# RH043_2.net
KiCad netlist of a schematic drawn in EAGLE
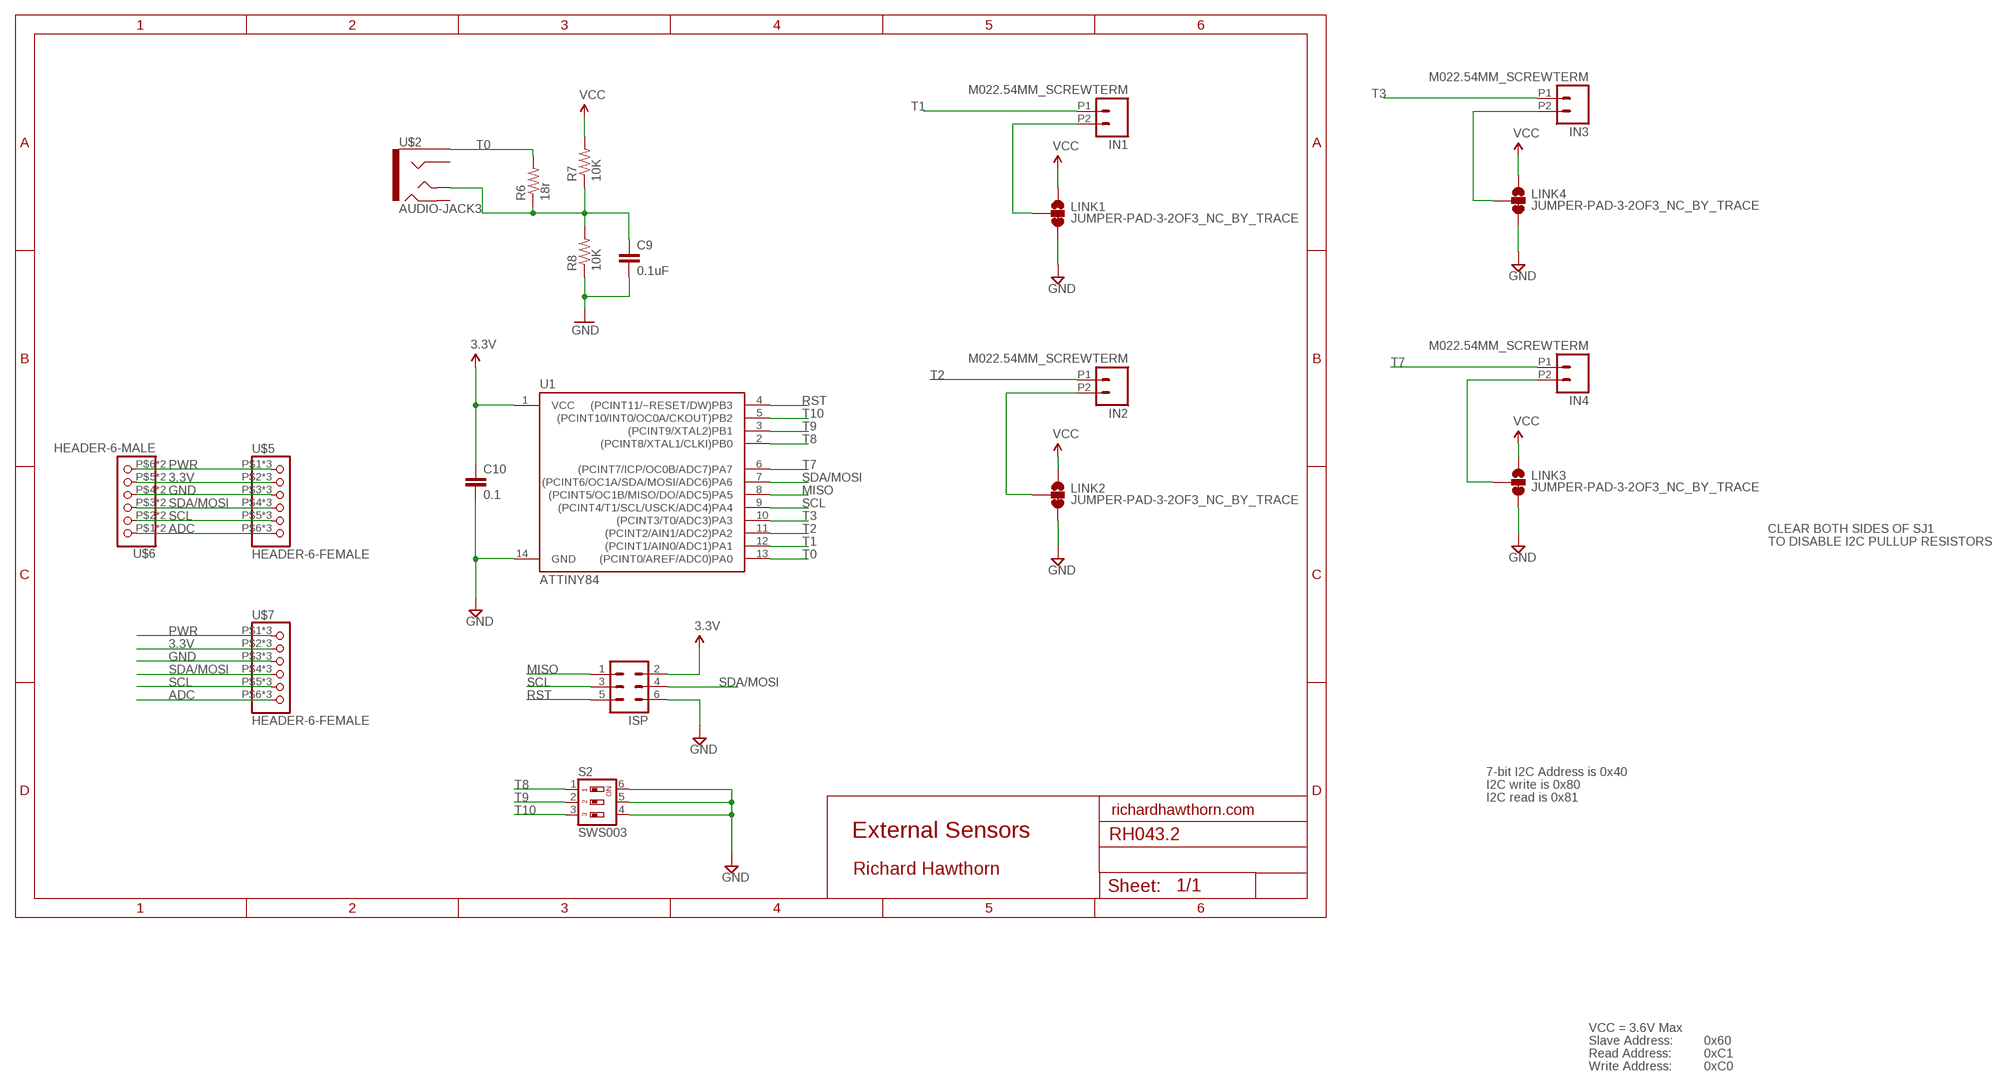
[diagram p0: schematic, sheet 1]

(export (version "E")
  (design (tool "Eeschema 10.0.6"))
  (components
    (comp (ref "C9")
      (value "0.1uF")
      (footprint "eagle-import:0603-CAP")
      (libsource (lib "eagle-import") (part "SparkFun_CAP0603-CAP"))
    )
    (comp (ref "C10")
      (value "0.1")
      (footprint "eagle-import:0603-CAP")
      (libsource (lib "eagle-import") (part "CAP0603-CAP"))
    )
    (comp (ref "IN1")
      (value "M022.54MM_SCREWTERM")
      (footprint "eagle-import:1X02_2.54_SCREWTERM")
      (libsource (lib "eagle-import") (part "M022.54MM_SCREWTERM"))
    )
    (comp (ref "IN2")
      (value "M022.54MM_SCREWTERM")
      (footprint "eagle-import:1X02_2.54_SCREWTERM")
      (libsource (lib "eagle-import") (part "M022.54MM_SCREWTERM"))
    )
    (comp (ref "IN3")
      (value "M022.54MM_SCREWTERM")
      (footprint "eagle-import:1X02_2.54_SCREWTERM")
      (libsource (lib "eagle-import") (part "M022.54MM_SCREWTERM"))
    )
    (comp (ref "IN4")
      (value "M022.54MM_SCREWTERM")
      (footprint "eagle-import:1X02_2.54_SCREWTERM")
      (libsource (lib "eagle-import") (part "M022.54MM_SCREWTERM"))
    )
    (comp (ref "ISP")
      (value "MA03-2")
      (footprint "eagle-import:MA03-2")
      (libsource (lib "eagle-import") (part "MA03-2"))
    )
    (comp (ref "LINK1")
      (value "JUMPER-PAD-3-2OF3_NC_BY_TRACE")
      (footprint "eagle-import:PAD-JUMPER-3-2OF3_NC_BY_TRACE_YES_SILK_FULL_BOX")
      (libsource (lib "eagle-import") (part "JUMPER-PAD-3-2OF3_NC_BY_TRACE"))
    )
    (comp (ref "LINK2")
      (value "JUMPER-PAD-3-2OF3_NC_BY_TRACE")
      (footprint "eagle-import:PAD-JUMPER-3-2OF3_NC_BY_TRACE_YES_SILK_FULL_BOX")
      (libsource (lib "eagle-import") (part "JUMPER-PAD-3-2OF3_NC_BY_TRACE"))
    )
    (comp (ref "LINK3")
      (value "JUMPER-PAD-3-2OF3_NC_BY_TRACE")
      (footprint "eagle-import:PAD-JUMPER-3-2OF3_NC_BY_TRACE_YES_SILK_FULL_BOX")
      (libsource (lib "eagle-import") (part "JUMPER-PAD-3-2OF3_NC_BY_TRACE"))
    )
    (comp (ref "LINK4")
      (value "JUMPER-PAD-3-2OF3_NC_BY_TRACE")
      (footprint "eagle-import:PAD-JUMPER-3-2OF3_NC_BY_TRACE_YES_SILK_FULL_BOX")
      (libsource (lib "eagle-import") (part "JUMPER-PAD-3-2OF3_NC_BY_TRACE"))
    )
    (comp (ref "R6")
      (value "18r")
      (footprint "eagle-import:0603-RES")
      (libsource (lib "eagle-import") (part "RESISTOR0603-RES"))
    )
    (comp (ref "R7")
      (value "10K")
      (footprint "eagle-import:0603-RES")
      (libsource (lib "eagle-import") (part "RESISTOR0603-RES"))
    )
    (comp (ref "R8")
      (value "10K")
      (footprint "eagle-import:0603-RES")
      (libsource (lib "eagle-import") (part "RESISTOR0603-RES"))
    )
    (comp (ref "S2")
      (value "SWS003")
      (footprint "eagle-import:SMS-003")
      (libsource (lib "eagle-import") (part "SWS003"))
    )
    (comp (ref "U$2")
      (value "AUDIO-JACK3")
      (footprint "eagle-import:AUDIO-JACK-TRRS-SMD")
      (libsource (lib "eagle-import") (part "AUDIO-JACK3"))
    )
    (comp (ref "U$5")
      (value "HEADER-6-FEMALE")
      (footprint "eagle-import:2MMHEADER6")
      (libsource (lib "eagle-import") (part "HEADER-6-FEMALE"))
    )
    (comp (ref "U$6")
      (value "HEADER-6-MALE")
      (footprint "eagle-import:2MMHEADERPIN6")
      (libsource (lib "eagle-import") (part "HEADER-6-MALE"))
    )
    (comp (ref "U$7")
      (value "HEADER-6-FEMALE")
      (footprint "eagle-import:2MMHEADER6")
      (libsource (lib "eagle-import") (part "HEADER-6-FEMALE"))
    )
    (comp (ref "U1")
      (value "ATTINY84")
      (footprint "eagle-import:SO14")
      (libsource (lib "eagle-import") (part "ATTINY84"))
    )
  )
  (nets
    (net (code "1") (name "/ADC") (class "Default")
      (node (ref "U$5") (pin "P$14") (pinfunction "6_P$14") (pintype "passive"))
      (node (ref "U$5") (pin "P$22") (pinfunction "6_P$22") (pintype "passive"))
      (node (ref "U$5") (pin "P$6") (pinfunction "6_P$6") (pintype "passive"))
      (node (ref "U$6") (pin "P$1") (pinfunction "1_P$1") (pintype "passive"))
      (node (ref "U$6") (pin "P$9") (pinfunction "1_P$9") (pintype "passive"))
      (node (ref "U$7") (pin "P$14") (pinfunction "6_P$14") (pintype "passive"))
      (node (ref "U$7") (pin "P$22") (pinfunction "6_P$22") (pintype "passive"))
      (node (ref "U$7") (pin "P$6") (pinfunction "6_P$6") (pintype "passive"))
    )
    (net (code "2") (name "/MISO") (class "Default")
      (node (ref "ISP") (pin "1") (pinfunction "1_1") (pintype "passive"))
      (node (ref "U1") (pin "8") (pinfunction "(PCINT5/OC1B/MISO/DO/ADC5)PA5_8") (pintype "bidirectional"))
    )
    (net (code "3") (name "/PWR") (class "Default")
      (node (ref "U$5") (pin "P$1") (pinfunction "1_P$1") (pintype "passive"))
      (node (ref "U$5") (pin "P$17") (pinfunction "1_P$17") (pintype "passive"))
      (node (ref "U$5") (pin "P$9") (pinfunction "1_P$9") (pintype "passive"))
      (node (ref "U$6") (pin "P$14") (pinfunction "6_P$14") (pintype "passive"))
      (node (ref "U$6") (pin "P$6") (pinfunction "6_P$6") (pintype "passive"))
      (node (ref "U$7") (pin "P$1") (pinfunction "1_P$1") (pintype "passive"))
      (node (ref "U$7") (pin "P$17") (pinfunction "1_P$17") (pintype "passive"))
      (node (ref "U$7") (pin "P$9") (pinfunction "1_P$9") (pintype "passive"))
    )
    (net (code "4") (name "/RST") (class "Default")
      (node (ref "ISP") (pin "5") (pinfunction "5_5") (pintype "passive"))
      (node (ref "U1") (pin "4") (pinfunction "(PCINT11/~{RESET/DW})PB3_4") (pintype "bidirectional"))
    )
    (net (code "5") (name "/SCL") (class "Default")
      (node (ref "ISP") (pin "3") (pinfunction "3_3") (pintype "passive"))
      (node (ref "U$5") (pin "P$13") (pinfunction "5_P$13") (pintype "passive"))
      (node (ref "U$5") (pin "P$21") (pinfunction "5_P$21") (pintype "passive"))
      (node (ref "U$5") (pin "P$5") (pinfunction "5_P$5") (pintype "passive"))
      (node (ref "U$6") (pin "P$10") (pinfunction "2_P$10") (pintype "passive"))
      (node (ref "U$6") (pin "P$2") (pinfunction "2_P$2") (pintype "passive"))
      (node (ref "U$7") (pin "P$13") (pinfunction "5_P$13") (pintype "passive"))
      (node (ref "U$7") (pin "P$21") (pinfunction "5_P$21") (pintype "passive"))
      (node (ref "U$7") (pin "P$5") (pinfunction "5_P$5") (pintype "passive"))
      (node (ref "U1") (pin "9") (pinfunction "(PCINT4/T1/SCL/USCK/ADC4)PA4_9") (pintype "bidirectional"))
    )
    (net (code "6") (name "/SDA{slash}MOSI") (class "Default")
      (node (ref "ISP") (pin "4") (pinfunction "4_4") (pintype "passive"))
      (node (ref "U$5") (pin "P$12") (pinfunction "4_P$12") (pintype "passive"))
      (node (ref "U$5") (pin "P$20") (pinfunction "4_P$20") (pintype "passive"))
      (node (ref "U$5") (pin "P$4") (pinfunction "4_P$4") (pintype "passive"))
      (node (ref "U$6") (pin "P$11") (pinfunction "3_P$11") (pintype "passive"))
      (node (ref "U$6") (pin "P$3") (pinfunction "3_P$3") (pintype "passive"))
      (node (ref "U$7") (pin "P$12") (pinfunction "4_P$12") (pintype "passive"))
      (node (ref "U$7") (pin "P$20") (pinfunction "4_P$20") (pintype "passive"))
      (node (ref "U$7") (pin "P$4") (pinfunction "4_P$4") (pintype "passive"))
      (node (ref "U1") (pin "7") (pinfunction "(PCINT6/OC1A/SDA/MOSI/ADC6)PA6_7") (pintype "bidirectional"))
    )
    (net (code "7") (name "/T0") (class "Default")
      (node (ref "R6") (pin "2") (pinfunction "2_2") (pintype "passive"))
      (node (ref "U$2") (pin "EARTH") (pinfunction "EARTH_EARTH") (pintype "bidirectional"))
      (node (ref "U1") (pin "13") (pinfunction "(PCINT0/AREF/ADC0)PA0_13") (pintype "bidirectional"))
    )
    (net (code "8") (name "/T1") (class "Default")
      (node (ref "IN1") (pin "P1") (pinfunction "1_P1") (pintype "passive"))
      (node (ref "U1") (pin "12") (pinfunction "(PCINT1/AIN0/ADC1)PA1_12") (pintype "bidirectional"))
    )
    (net (code "9") (name "/T2") (class "Default")
      (node (ref "IN2") (pin "P1") (pinfunction "1_P1") (pintype "passive"))
      (node (ref "U1") (pin "11") (pinfunction "(PCINT2/AIN1/ADC2)PA2_11") (pintype "bidirectional"))
    )
    (net (code "10") (name "/T3") (class "Default")
      (node (ref "IN3") (pin "P1") (pinfunction "1_P1") (pintype "passive"))
      (node (ref "U1") (pin "10") (pinfunction "(PCINT3/T0/ADC3)PA3_10") (pintype "bidirectional"))
    )
    (net (code "11") (name "/T7") (class "Default")
      (node (ref "IN4") (pin "P1") (pinfunction "1_P1") (pintype "passive"))
      (node (ref "U1") (pin "6") (pinfunction "(PCINT7/ICP/OC0B/ADC7)PA7_6") (pintype "bidirectional"))
    )
    (net (code "12") (name "/T8") (class "Default")
      (node (ref "S2") (pin "1") (pinfunction "1_1") (pintype "passive"))
      (node (ref "U1") (pin "2") (pinfunction "(PCINT8/XTAL1/CLKI)PB0_2") (pintype "bidirectional"))
    )
    (net (code "13") (name "/T9") (class "Default")
      (node (ref "S2") (pin "2") (pinfunction "2_2") (pintype "passive"))
      (node (ref "U1") (pin "3") (pinfunction "(PCINT9/XTAL2)PB1_3") (pintype "bidirectional"))
    )
    (net (code "14") (name "/T10") (class "Default")
      (node (ref "S2") (pin "3") (pinfunction "3_3") (pintype "passive"))
      (node (ref "U1") (pin "5") (pinfunction "(PCINT10/INT0/OC0A/CKOUT)PB2_5") (pintype "bidirectional"))
    )
    (net (code "15") (name "3.3V") (class "Default")
      (node (ref "C10") (pin "1") (pinfunction "1_1") (pintype "passive"))
      (node (ref "ISP") (pin "2") (pinfunction "2_2") (pintype "passive"))
      (node (ref "LINK1") (pin "1") (pinfunction "1_1") (pintype "passive"))
      (node (ref "LINK2") (pin "1") (pinfunction "1_1") (pintype "passive"))
      (node (ref "LINK3") (pin "1") (pinfunction "1_1") (pintype "passive"))
      (node (ref "LINK4") (pin "1") (pinfunction "1_1") (pintype "passive"))
      (node (ref "R7") (pin "2") (pinfunction "2_2") (pintype "passive"))
      (node (ref "U$5") (pin "P$10") (pinfunction "2_P$10") (pintype "passive"))
      (node (ref "U$5") (pin "P$18") (pinfunction "2_P$18") (pintype "passive"))
      (node (ref "U$5") (pin "P$2") (pinfunction "2_P$2") (pintype "passive"))
      (node (ref "U$6") (pin "P$13") (pinfunction "5_P$13") (pintype "passive"))
      (node (ref "U$6") (pin "P$5") (pinfunction "5_P$5") (pintype "passive"))
      (node (ref "U$7") (pin "P$10") (pinfunction "2_P$10") (pintype "passive"))
      (node (ref "U$7") (pin "P$18") (pinfunction "2_P$18") (pintype "passive"))
      (node (ref "U$7") (pin "P$2") (pinfunction "2_P$2") (pintype "passive"))
      (node (ref "U1") (pin "1") (pinfunction "VCC_1") (pintype "bidirectional"))
    )
    (net (code "16") (name "GND") (class "Default")
      (node (ref "C10") (pin "2") (pinfunction "2_2") (pintype "passive"))
      (node (ref "C9") (pin "2") (pinfunction "2_2") (pintype "passive"))
      (node (ref "ISP") (pin "6") (pinfunction "6_6") (pintype "passive"))
      (node (ref "LINK1") (pin "3") (pinfunction "3_3") (pintype "passive"))
      (node (ref "LINK2") (pin "3") (pinfunction "3_3") (pintype "passive"))
      (node (ref "LINK3") (pin "3") (pinfunction "3_3") (pintype "passive"))
      (node (ref "LINK4") (pin "3") (pinfunction "3_3") (pintype "passive"))
      (node (ref "R8") (pin "1") (pinfunction "1_1") (pintype "passive"))
      (node (ref "S2") (pin "4") (pinfunction "4_4") (pintype "passive"))
      (node (ref "S2") (pin "5") (pinfunction "5_5") (pintype "passive"))
      (node (ref "S2") (pin "6") (pinfunction "6_6") (pintype "passive"))
      (node (ref "U$5") (pin "P$11") (pinfunction "3_P$11") (pintype "passive"))
      (node (ref "U$5") (pin "P$19") (pinfunction "3_P$19") (pintype "passive"))
      (node (ref "U$5") (pin "P$3") (pinfunction "3_P$3") (pintype "passive"))
      (node (ref "U$6") (pin "P$12") (pinfunction "4_P$12") (pintype "passive"))
      (node (ref "U$6") (pin "P$4") (pinfunction "4_P$4") (pintype "passive"))
      (node (ref "U$7") (pin "P$11") (pinfunction "3_P$11") (pintype "passive"))
      (node (ref "U$7") (pin "P$19") (pinfunction "3_P$19") (pintype "passive"))
      (node (ref "U$7") (pin "P$3") (pinfunction "3_P$3") (pintype "passive"))
      (node (ref "U1") (pin "14") (pinfunction "GND_14") (pintype "bidirectional"))
    )
    (net (code "17") (name "Net-(C9-Pad1)") (class "Default")
      (node (ref "C9") (pin "1") (pinfunction "1_1") (pintype "passive"))
      (node (ref "R6") (pin "1") (pinfunction "1_1") (pintype "passive"))
      (node (ref "R7") (pin "1") (pinfunction "1_1") (pintype "passive"))
      (node (ref "R8") (pin "2") (pinfunction "2_2") (pintype "passive"))
      (node (ref "U$2") (pin "TIP") (pinfunction "TIP_TIP") (pintype "bidirectional"))
    )
    (net (code "18") (name "Net-(IN1-2)") (class "Default")
      (node (ref "IN1") (pin "P2") (pinfunction "2_P2") (pintype "passive"))
      (node (ref "LINK1") (pin "2") (pinfunction "2_2") (pintype "passive"))
    )
    (net (code "19") (name "Net-(IN2-2)") (class "Default")
      (node (ref "IN2") (pin "P2") (pinfunction "2_P2") (pintype "passive"))
      (node (ref "LINK2") (pin "2") (pinfunction "2_2") (pintype "passive"))
    )
    (net (code "20") (name "Net-(IN3-2)") (class "Default")
      (node (ref "IN3") (pin "P2") (pinfunction "2_P2") (pintype "passive"))
      (node (ref "LINK4") (pin "2") (pinfunction "2_2") (pintype "passive"))
    )
    (net (code "21") (name "Net-(IN4-2)") (class "Default")
      (node (ref "IN4") (pin "P2") (pinfunction "2_P2") (pintype "passive"))
      (node (ref "LINK3") (pin "2") (pinfunction "2_2") (pintype "passive"))
    )
    (net (code "22") (name "unconnected-(U$2-PadRING1)") (class "Default")
      (node (ref "U$2") (pin "RING1") (pinfunction "RING1_RING1") (pintype "bidirectional"))
    )
    (net (code "23") (name "unconnected-(U$2-PadRING2)") (class "Default")
      (node (ref "U$2") (pin "RING2") (pinfunction "RING2_RING2") (pintype "bidirectional"))
    )
  )
)
